# SCH_RTC6705_V0_1_2025-12-21.net
KiCad netlist of a schematic drawn in EasyEDA
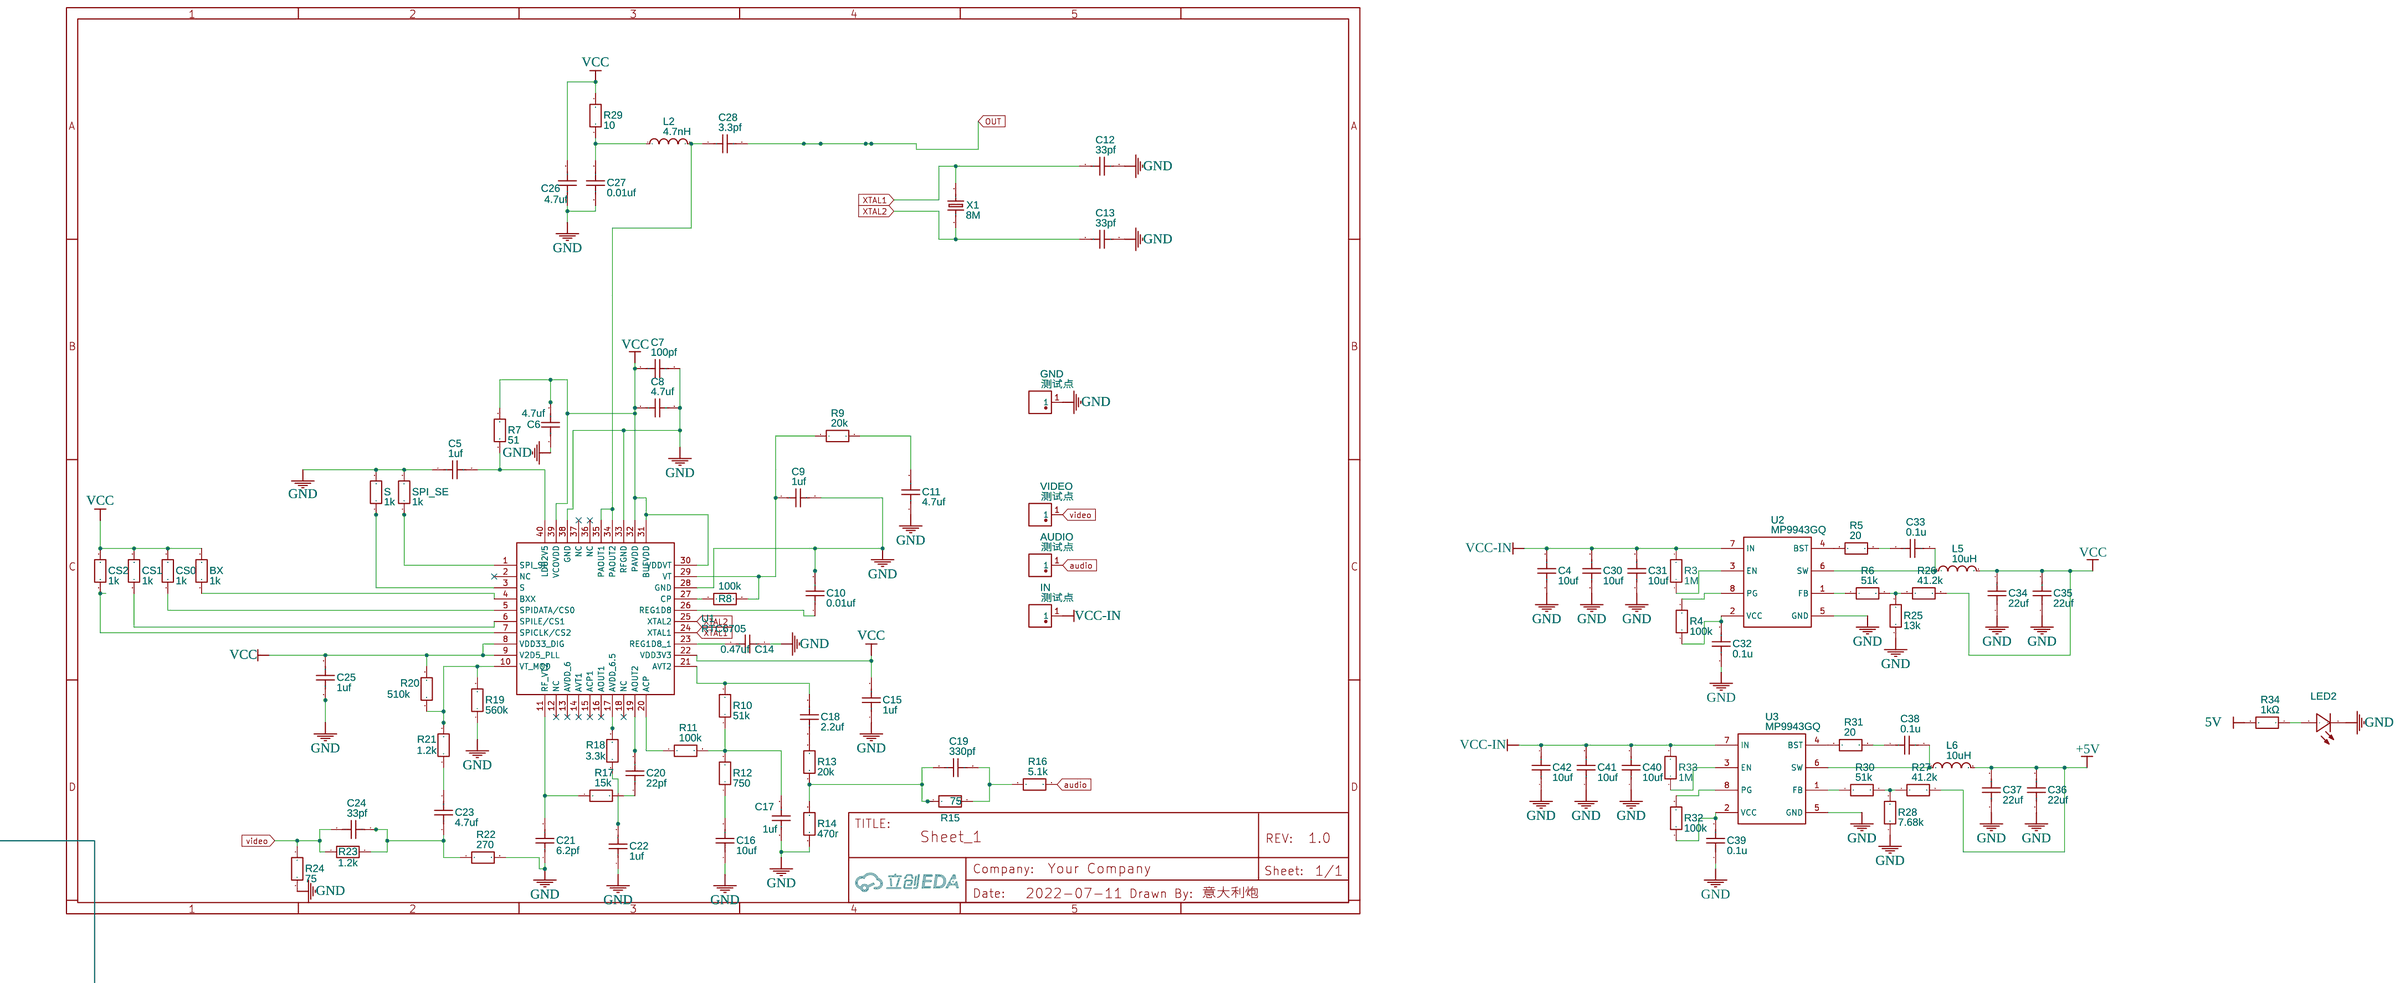
[diagram p0: 稳压和调频]
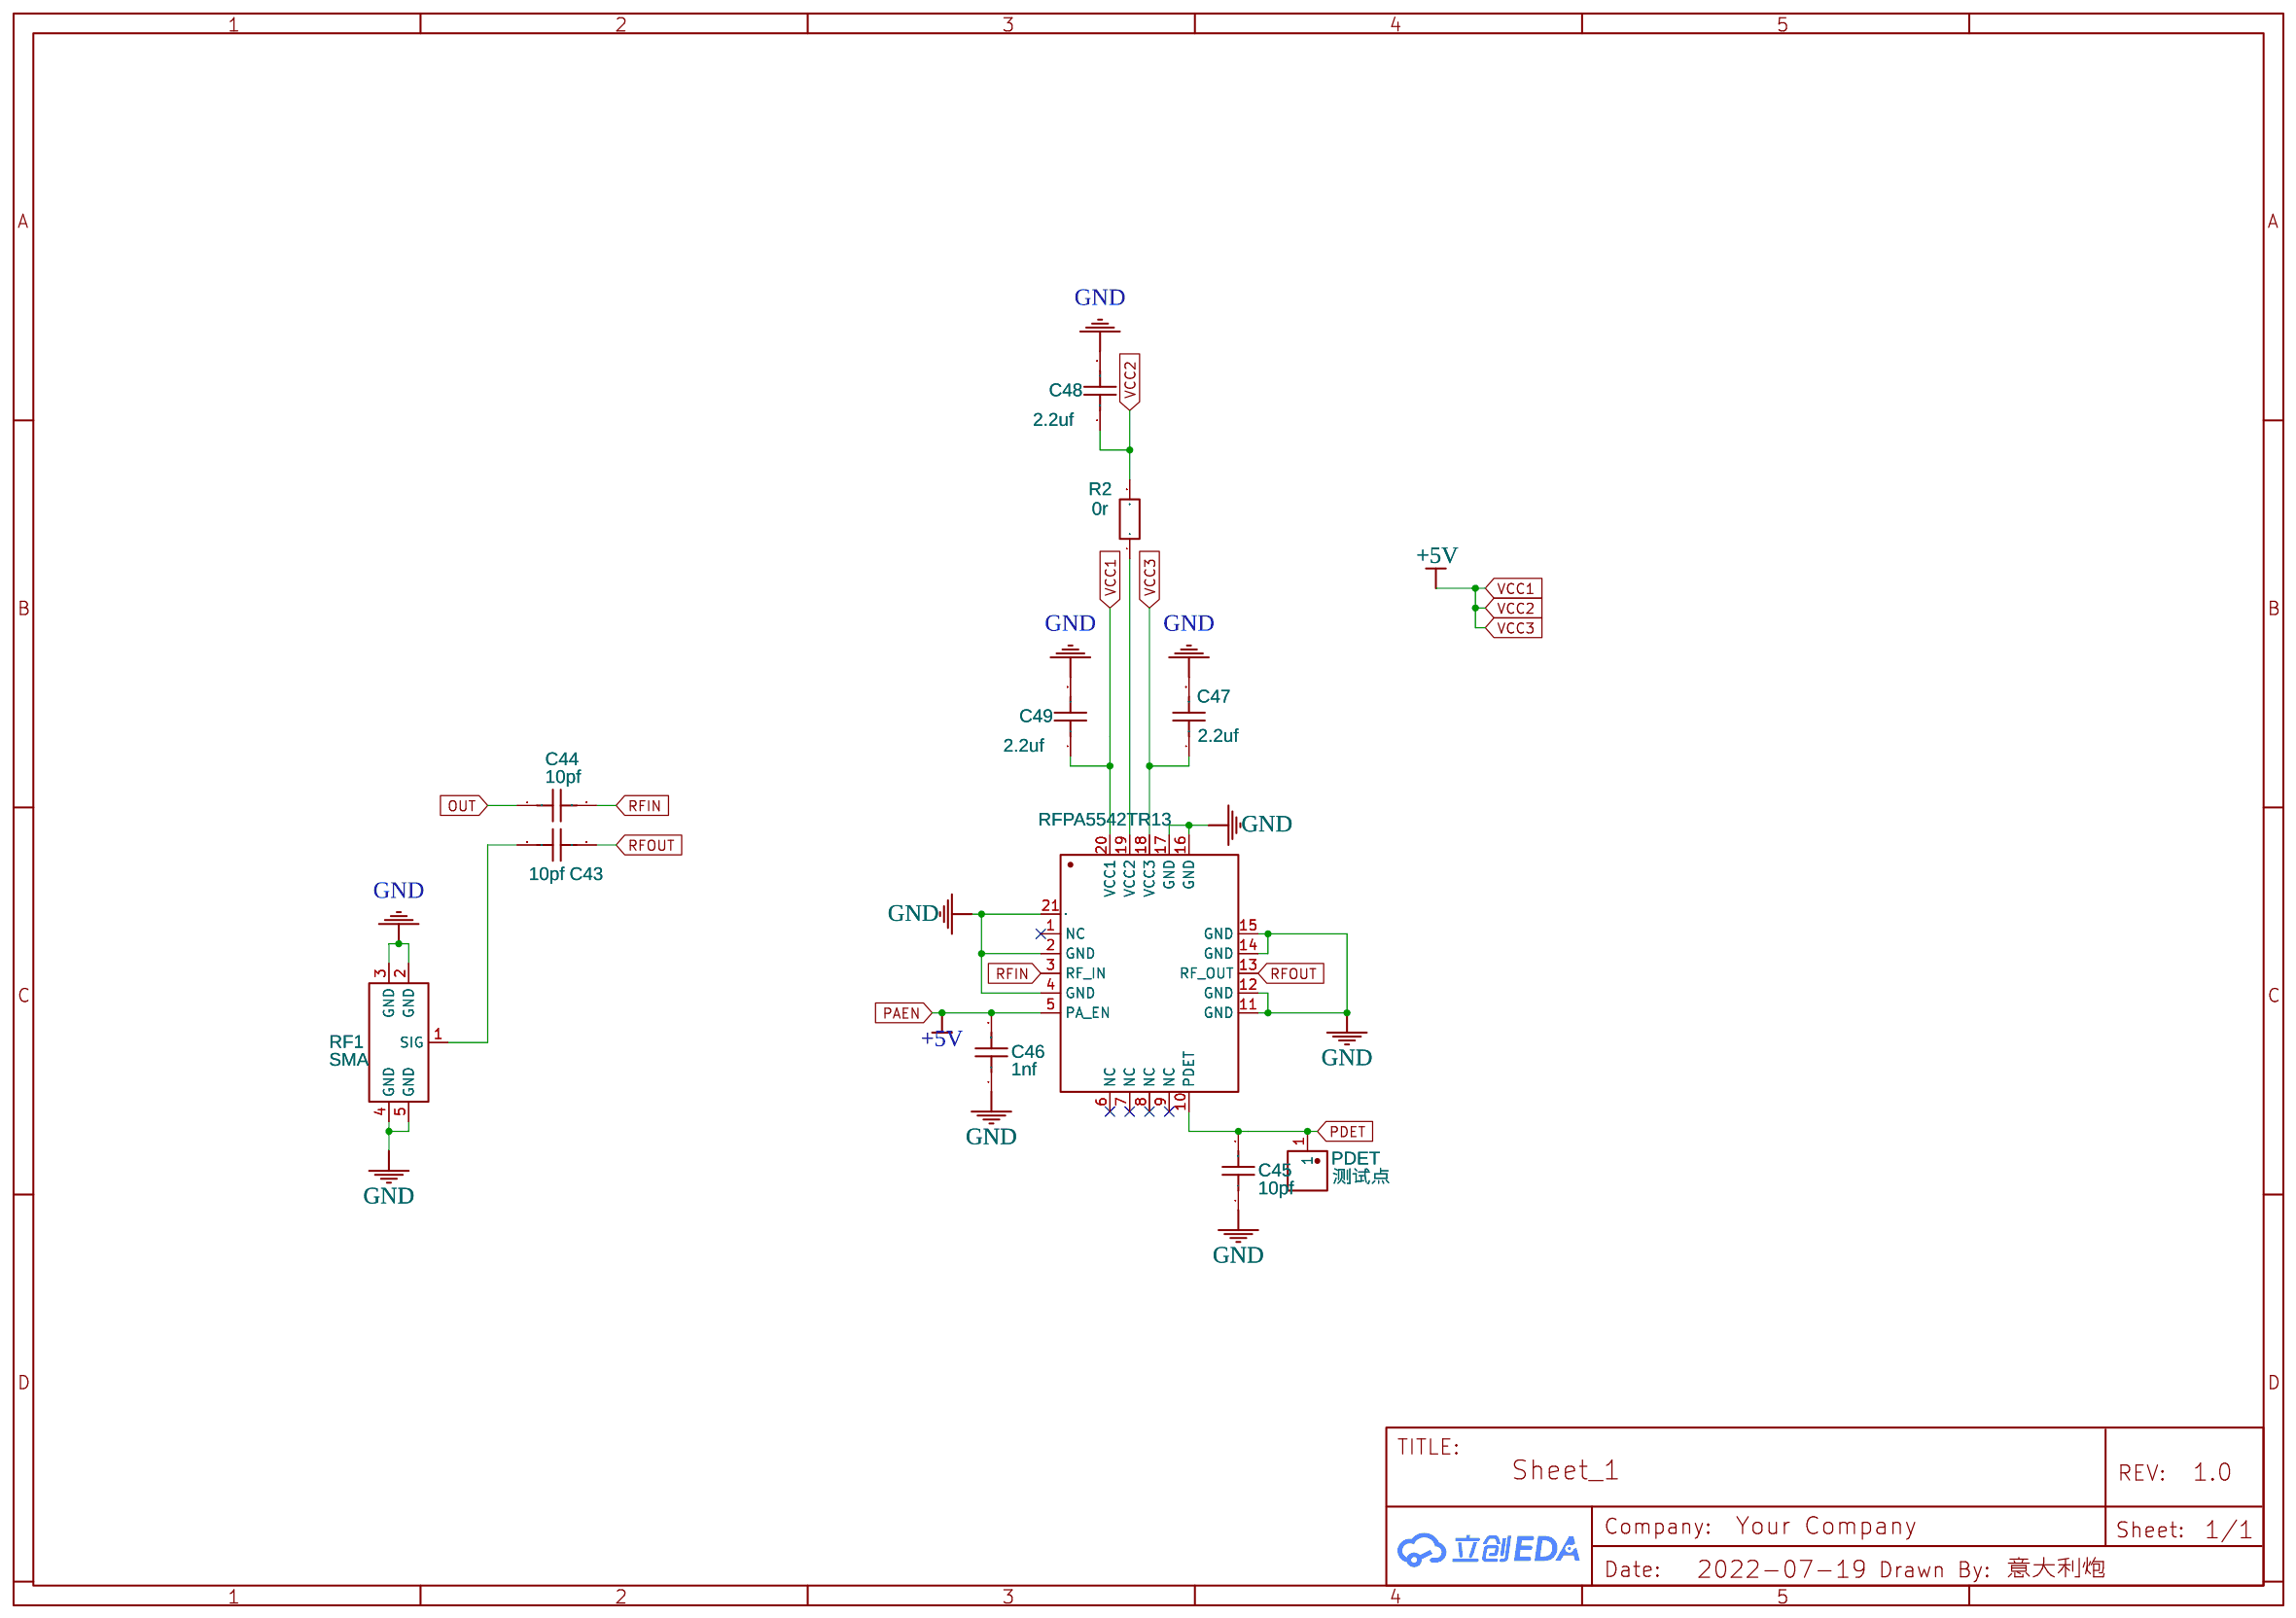
[diagram p1: 2W放大器]

(export (version "E")
  (design (tool "Eeschema 10.0.6"))
  (components
    (comp (ref "AUDIO") (value "测试点") (libsource (lib "") (part "测试点_3")))
    (comp (ref "BX") (value "1k") (libsource (lib "") (part "R_0603_EU_5")))
    (comp (ref "C4") (value "10uf") (libsource (lib "") (part "C_0603_US_1")))
    (comp (ref "C5") (value "1uf") (libsource (lib "") (part "C_0603_US")))
    (comp (ref "C6") (value "4.7uf") (libsource (lib "") (part "C_0603_US_1")))
    (comp (ref "C7") (value "100pf") (libsource (lib "") (part "C_0603_US")))
    (comp (ref "C8") (value "4.7uf") (libsource (lib "") (part "C_0603_US")))
    (comp (ref "C9") (value "1uf") (libsource (lib "") (part "C_0603_US")))
    (comp (ref "C10") (value "0.01uf") (libsource (lib "") (part "C_0603_US_1")))
    (comp (ref "C11") (value "4.7uf") (libsource (lib "") (part "C_0603_US_1")))
    (comp (ref "C12") (value "33pf") (libsource (lib "") (part "C_0603_US")))
    (comp (ref "C13") (value "33pf") (libsource (lib "") (part "C_0603_US")))
    (comp (ref "C14") (value "0.47uf") (libsource (lib "") (part "C_0603_US")))
    (comp (ref "C15") (value "1uf") (libsource (lib "") (part "C_0603_US_1")))
    (comp (ref "C16") (value "10uf") (libsource (lib "") (part "C_0603_US_1")))
    (comp (ref "C17") (value "1uf") (libsource (lib "") (part "C_0603_US_1")))
    (comp (ref "C18") (value "2.2uf") (libsource (lib "") (part "C_0603_US_1")))
    (comp (ref "C19") (value "330pf") (libsource (lib "") (part "C_0603_US")))
    (comp (ref "C20") (value "22pf") (libsource (lib "") (part "C_0603_US_1")))
    (comp (ref "C21") (value "6.2pf") (libsource (lib "") (part "C_0603_US_1")))
    (comp (ref "C22") (value "1uf") (libsource (lib "") (part "C_0603_US_1")))
    (comp (ref "C23") (value "4.7uf") (libsource (lib "") (part "C_0603_US_1")))
    (comp (ref "C24") (value "33pf") (libsource (lib "") (part "C_0603_US")))
    (comp (ref "C25") (value "1uf") (libsource (lib "") (part "C_0603_US_1")))
    (comp (ref "C26") (value "4.7uf") (libsource (lib "") (part "C_0603_US_1")))
    (comp (ref "C27") (value "0.01uf") (libsource (lib "") (part "C_0603_US_1")))
    (comp (ref "C28") (value "3.3pf") (libsource (lib "") (part "C_0603_US")))
    (comp (ref "C30") (value "10uf") (libsource (lib "") (part "C_0603_US_1")))
    (comp (ref "C31") (value "10uf") (libsource (lib "") (part "C_0603_US_1")))
    (comp (ref "C32") (value "0.1u") (libsource (lib "") (part "C_0603_US_1")))
    (comp (ref "C33") (value "0.1u") (libsource (lib "") (part "C_0603_US")))
    (comp (ref "C34") (value "22uf") (libsource (lib "") (part "C_0805_US")))
    (comp (ref "C35") (value "22uf") (libsource (lib "") (part "C_0805_US")))
    (comp (ref "C36") (value "22uf") (libsource (lib "") (part "C_0805_US")))
    (comp (ref "C37") (value "22uf") (libsource (lib "") (part "C_0805_US")))
    (comp (ref "C38") (value "0.1u") (libsource (lib "") (part "C_0603_US")))
    (comp (ref "C39") (value "0.1u") (libsource (lib "") (part "C_0603_US_1")))
    (comp (ref "C40") (value "10uf") (libsource (lib "") (part "C_0603_US_1")))
    (comp (ref "C41") (value "10uf") (libsource (lib "") (part "C_0603_US_1")))
    (comp (ref "C42") (value "10uf") (libsource (lib "") (part "C_0603_US_1")))
    (comp (ref "CS0") (value "1k") (libsource (lib "") (part "R_0603_EU")))
    (comp (ref "CS1") (value "1k") (libsource (lib "") (part "R_0603_EU")))
    (comp (ref "CS2") (value "1k") (libsource (lib "") (part "R_0603_EU")))
    (comp (ref "GND") (value "测试点") (libsource (lib "") (part "测试点_1")))
    (comp (ref "IN") (value "测试点") (libsource (lib "") (part "测试点")))
    (comp (ref "L2")
      (value "4.7nH")
      (fields (field (name "Manufacturer Part") "SDCL1608C4N7STDF") (field (name "Manufacturer") "Sunlord"))
      (libsource (lib "") (part "SDCL1608C4N7STDF"))
    )
    (comp (ref "L5")
      (value "10uH")
      (fields (field (name "Manufacturer Part") "PHC0420-100M-T") (field (name "Manufacturer") "EMTEK"))
      (libsource (lib "") (part "PHC0420-100M-T"))
    )
    (comp (ref "L6")
      (value "10uH")
      (fields (field (name "Manufacturer Part") "PHC0420-100M-T") (field (name "Manufacturer") "EMTEK"))
      (libsource (lib "") (part "PHC0420-100M-T"))
    )
    (comp (ref "LED2")
      (value "LTST-C170KRKT")
      (fields (field (name "Manufacturer") "LITEON"))
      (libsource (lib "") (part "LTST-C170KRKT"))
    )
    (comp (ref "R3") (value "1M") (libsource (lib "") (part "R_0603_EU_2")))
    (comp (ref "R4") (value "100k") (libsource (lib "") (part "R_0603_EU_2")))
    (comp (ref "R5") (value "20") (libsource (lib "") (part "R_0603_EU_1")))
    (comp (ref "R6") (value "51k") (libsource (lib "") (part "R_0402_EU")))
    (comp (ref "R7") (value "51") (libsource (lib "") (part "R_0603_EU_2")))
    (comp (ref "R8") (value "100k") (libsource (lib "") (part "R_0603_EU_1")))
    (comp (ref "R9") (value "20k") (libsource (lib "") (part "R_0603_EU_1")))
    (comp (ref "R10") (value "51k") (libsource (lib "") (part "R_0603_EU_2")))
    (comp (ref "R11") (value "100k") (libsource (lib "") (part "R_0603_EU_1")))
    (comp (ref "R12") (value "750") (libsource (lib "") (part "R_0603_EU_2")))
    (comp (ref "R13") (value "20k") (libsource (lib "") (part "R_0603_EU_2")))
    (comp (ref "R14") (value "470r") (libsource (lib "") (part "R_0603_EU_2")))
    (comp (ref "R15") (value "75") (libsource (lib "") (part "R_0603_EU_1")))
    (comp (ref "R16") (value "5.1k") (libsource (lib "") (part "R_0603_EU_1")))
    (comp (ref "R17") (value "15k") (libsource (lib "") (part "R_0603_EU_1")))
    (comp (ref "R18") (value "3.3k") (libsource (lib "") (part "R_0603_EU_2")))
    (comp (ref "R19") (value "560k") (libsource (lib "") (part "R_0603_EU_2")))
    (comp (ref "R20") (value "510k") (libsource (lib "") (part "R_0603_EU_2")))
    (comp (ref "R21") (value "1.2k") (libsource (lib "") (part "R_0603_EU_2")))
    (comp (ref "R22") (value "270") (libsource (lib "") (part "R_0603_EU_1")))
    (comp (ref "R23") (value "1.2k") (libsource (lib "") (part "R_0603_EU_1")))
    (comp (ref "R24") (value "75") (libsource (lib "") (part "R_0603_EU_2")))
    (comp (ref "R25") (value "13k") (libsource (lib "") (part "R_0402_EU_1")))
    (comp (ref "R26") (value "41.2k") (libsource (lib "") (part "R_0402_EU")))
    (comp (ref "R27") (value "41.2k") (libsource (lib "") (part "R_0402_EU")))
    (comp (ref "R28") (value "7.68k") (libsource (lib "") (part "R_0402_EU_1")))
    (comp (ref "R29") (value "10") (libsource (lib "") (part "R_0603_EU_2")))
    (comp (ref "R30") (value "51k") (libsource (lib "") (part "R_0402_EU")))
    (comp (ref "R31") (value "20") (libsource (lib "") (part "R_0603_EU_1")))
    (comp (ref "R32") (value "100k") (libsource (lib "") (part "R_0603_EU_2")))
    (comp (ref "R33") (value "1M") (libsource (lib "") (part "R_0603_EU_2")))
    (comp (ref "R34")
      (value "1kΩ")
      (fields (field (name "Manufacturer Part") "ESR10EZPF1001") (field (name "Manufacturer") "ROHM Semicon"))
      (libsource (lib "") (part "ESR10EZPF1001"))
    )
    (comp (ref "S") (value "1k") (libsource (lib "") (part "R_0603_EU_4")))
    (comp (ref "SPI_SE") (value "1k") (libsource (lib "") (part "R_0603_EU_3")))
    (comp (ref "U1")
      (value "RTC6705")
      (fields (field (name "Manufacturer") "Richwave"))
      (libsource (lib "") (part "RTC6705"))
    )
    (comp (ref "U2")
      (value "MP9943GQ")
      (fields (field (name "Manufacturer") "MPS"))
      (libsource (lib "") (part "MP9943GQ"))
    )
    (comp (ref "U3")
      (value "MP9943GQ")
      (fields (field (name "Manufacturer") "MPS"))
      (libsource (lib "") (part "MP9943GQ"))
    )
    (comp (ref "VIDEO") (value "测试点") (libsource (lib "") (part "测试点_2")))
    (comp (ref "X1")
      (value "8M")
      (fields (field (name "Manufacturer Part") "8M晶振"))
      (libsource (lib "") (part "8M晶振_C9900021502"))
    )
    (comp (ref "C43") (value "10pf") (libsource (lib "") (part "C_0603_US")))
    (comp (ref "C44") (value "10pf") (libsource (lib "") (part "C_0603_US")))
    (comp (ref "C45") (value "10pf") (libsource (lib "") (part "C_0603_US_1")))
    (comp (ref "C46") (value "1nf") (libsource (lib "") (part "C_0603_US_1")))
    (comp (ref "C47") (value "2.2uf") (libsource (lib "") (part "C_0603_US_1")))
    (comp (ref "C48") (value "2.2uf") (libsource (lib "") (part "C_0603_US_1")))
    (comp (ref "C49") (value "2.2uf") (libsource (lib "") (part "C_0603_US_1")))
    (comp (ref "PDET") (value "测试点") (libsource (lib "") (part "测试点")))
    (comp (ref "R2") (value "0r") (libsource (lib "") (part "R_0603_EU")))
    (comp (ref "RF1")
      (value "SMA")
      (fields (field (name "Manufacturer Part") "HJ-SMA023") (field (name "Manufacturer") "皇捷"))
      (libsource (lib "") (part "SMA"))
    )
    (comp (ref "U5")
      (value "RFPA5542TR13")
      (fields (field (name "Manufacturer") "Qorvo"))
      (libsource (lib "") (part "RFPA5542TR13"))
    )
  )
  (nets
    (net (code "1") (name "5V") (class "Default")
      (node (ref "R34") (pin "2") (pinfunction "2_2") (pintype "unspecified"))
    )
    (net (code "2") (name "GND") (class "Default")
      (node (ref "C10") (pin "2") (pinfunction "2_2") (pintype "unspecified"))
      (node (ref "C11") (pin "1") (pinfunction "1_1") (pintype "unspecified"))
      (node (ref "C12") (pin "2") (pinfunction "2_2") (pintype "unspecified"))
      (node (ref "C13") (pin "2") (pinfunction "2_2") (pintype "unspecified"))
      (node (ref "C14") (pin "2") (pinfunction "2_2") (pintype "unspecified"))
      (node (ref "C15") (pin "1") (pinfunction "1_1") (pintype "unspecified"))
      (node (ref "C16") (pin "1") (pinfunction "1_1") (pintype "unspecified"))
      (node (ref "C17") (pin "1") (pinfunction "1_1") (pintype "unspecified"))
      (node (ref "C21") (pin "1") (pinfunction "1_1") (pintype "unspecified"))
      (node (ref "C22") (pin "1") (pinfunction "1_1") (pintype "unspecified"))
      (node (ref "C25") (pin "1") (pinfunction "1_1") (pintype "unspecified"))
      (node (ref "C26") (pin "1") (pinfunction "1_1") (pintype "unspecified"))
      (node (ref "C27") (pin "1") (pinfunction "1_1") (pintype "unspecified"))
      (node (ref "C30") (pin "1") (pinfunction "1_1") (pintype "unspecified"))
      (node (ref "C31") (pin "1") (pinfunction "1_1") (pintype "unspecified"))
      (node (ref "C32") (pin "1") (pinfunction "1_1") (pintype "unspecified"))
      (node (ref "C34") (pin "1") (pinfunction "1_1") (pintype "unspecified"))
      (node (ref "C35") (pin "1") (pinfunction "1_1") (pintype "unspecified"))
      (node (ref "C36") (pin "1") (pinfunction "1_1") (pintype "unspecified"))
      (node (ref "C37") (pin "1") (pinfunction "1_1") (pintype "unspecified"))
      (node (ref "C39") (pin "1") (pinfunction "1_1") (pintype "unspecified"))
      (node (ref "C4") (pin "1") (pinfunction "1_1") (pintype "unspecified"))
      (node (ref "C40") (pin "1") (pinfunction "1_1") (pintype "unspecified"))
      (node (ref "C41") (pin "1") (pinfunction "1_1") (pintype "unspecified"))
      (node (ref "C42") (pin "1") (pinfunction "1_1") (pintype "unspecified"))
      (node (ref "C45") (pin "1") (pinfunction "1_1") (pintype "unspecified"))
      (node (ref "C46") (pin "1") (pinfunction "1_1") (pintype "unspecified"))
      (node (ref "C47") (pin "2") (pinfunction "2_2") (pintype "unspecified"))
      (node (ref "C48") (pin "2") (pinfunction "2_2") (pintype "unspecified"))
      (node (ref "C49") (pin "2") (pinfunction "2_2") (pintype "unspecified"))
      (node (ref "C5") (pin "1") (pinfunction "1_1") (pintype "unspecified"))
      (node (ref "C6") (pin "1") (pinfunction "1_1") (pintype "unspecified"))
      (node (ref "C7") (pin "2") (pinfunction "2_2") (pintype "unspecified"))
      (node (ref "C8") (pin "2") (pinfunction "2_2") (pintype "unspecified"))
      (node (ref "C9") (pin "2") (pinfunction "2_2") (pintype "unspecified"))
      (node (ref "GND") (pin "1") (pinfunction "1_1") (pintype "unspecified"))
      (node (ref "LED2") (pin "1") (pinfunction "-_1") (pintype "unspecified"))
      (node (ref "R14") (pin "1") (pinfunction "1_1") (pintype "unspecified"))
      (node (ref "R19") (pin "1") (pinfunction "1_1") (pintype "unspecified"))
      (node (ref "R22") (pin "2") (pinfunction "2_2") (pintype "unspecified"))
      (node (ref "R24") (pin "1") (pinfunction "1_1") (pintype "unspecified"))
      (node (ref "R25") (pin "1") (pinfunction "1_1") (pintype "unspecified"))
      (node (ref "R28") (pin "1") (pinfunction "1_1") (pintype "unspecified"))
      (node (ref "RF1") (pin "2") (pinfunction "GND_2") (pintype "unspecified"))
      (node (ref "RF1") (pin "3") (pinfunction "GND_3") (pintype "unspecified"))
      (node (ref "RF1") (pin "4") (pinfunction "GND_4") (pintype "unspecified"))
      (node (ref "RF1") (pin "5") (pinfunction "GND_5") (pintype "unspecified"))
      (node (ref "S") (pin "2") (pinfunction "2_2") (pintype "unspecified"))
      (node (ref "SPI_SE") (pin "2") (pinfunction "2_2") (pintype "unspecified"))
      (node (ref "U1") (pin "28") (pinfunction "GND_28") (pintype "unspecified"))
      (node (ref "U1") (pin "33") (pinfunction "RFGND_33") (pintype "unspecified"))
      (node (ref "U1") (pin "38") (pinfunction "GND_38") (pintype "unspecified"))
      (node (ref "U2") (pin "5") (pinfunction "GND_5") (pintype "unspecified"))
      (node (ref "U3") (pin "5") (pinfunction "GND_5") (pintype "unspecified"))
      (node (ref "U5") (pin "11") (pinfunction "GND_11") (pintype "unspecified"))
      (node (ref "U5") (pin "12") (pinfunction "GND_12") (pintype "unspecified"))
      (node (ref "U5") (pin "14") (pinfunction "GND_14") (pintype "unspecified"))
      (node (ref "U5") (pin "15") (pinfunction "GND_15") (pintype "unspecified"))
      (node (ref "U5") (pin "16") (pinfunction "GND_16") (pintype "unspecified"))
      (node (ref "U5") (pin "17") (pinfunction "GND_17") (pintype "unspecified"))
      (node (ref "U5") (pin "2") (pinfunction "GND_2") (pintype "unspecified"))
      (node (ref "U5") (pin "21") (pinfunction "PAD_21") (pintype "unspecified"))
      (node (ref "U5") (pin "4") (pinfunction "GND_4") (pintype "unspecified"))
    )
    (net (code "3") (name "Net-(C11-Pad2)") (class "Default")
      (node (ref "C11") (pin "2") (pinfunction "2_2") (pintype "unspecified"))
      (node (ref "R9") (pin "2") (pinfunction "2_2") (pintype "unspecified"))
    )
    (net (code "4") (name "Net-(C16-Pad2)") (class "Default")
      (node (ref "C16") (pin "2") (pinfunction "2_2") (pintype "unspecified"))
      (node (ref "R12") (pin "1") (pinfunction "1_1") (pintype "unspecified"))
    )
    (net (code "5") (name "Net-(C17-Pad2)") (class "Default")
      (node (ref "C17") (pin "2") (pinfunction "2_2") (pintype "unspecified"))
      (node (ref "R10") (pin "1") (pinfunction "1_1") (pintype "unspecified"))
      (node (ref "R11") (pin "2") (pinfunction "2_2") (pintype "unspecified"))
      (node (ref "R12") (pin "2") (pinfunction "2_2") (pintype "unspecified"))
    )
    (net (code "6") (name "Net-(C18-Pad1)") (class "Default")
      (node (ref "C18") (pin "1") (pinfunction "1_1") (pintype "unspecified"))
      (node (ref "R13") (pin "2") (pinfunction "2_2") (pintype "unspecified"))
    )
    (net (code "7") (name "Net-(C19-Pad1)") (class "Default")
      (node (ref "C19") (pin "1") (pinfunction "1_1") (pintype "unspecified"))
      (node (ref "R13") (pin "1") (pinfunction "1_1") (pintype "unspecified"))
      (node (ref "R14") (pin "2") (pinfunction "2_2") (pintype "unspecified"))
      (node (ref "R15") (pin "1") (pinfunction "1_1") (pintype "unspecified"))
    )
    (net (code "8") (name "Net-(C19-Pad2)") (class "Default")
      (node (ref "C19") (pin "2") (pinfunction "2_2") (pintype "unspecified"))
      (node (ref "R15") (pin "2") (pinfunction "2_2") (pintype "unspecified"))
      (node (ref "R16") (pin "1") (pinfunction "1_1") (pintype "unspecified"))
    )
    (net (code "9") (name "Net-(C20-Pad1)") (class "Default")
      (node (ref "C20") (pin "1") (pinfunction "1_1") (pintype "unspecified"))
      (node (ref "R17") (pin "2") (pinfunction "2_2") (pintype "unspecified"))
    )
    (net (code "10") (name "Net-(C22-Pad2)") (class "Default")
      (node (ref "C22") (pin "2") (pinfunction "2_2") (pintype "unspecified"))
      (node (ref "R18") (pin "1") (pinfunction "1_1") (pintype "unspecified"))
    )
    (net (code "11") (name "Net-(C23-Pad1)") (class "Default")
      (node (ref "C23") (pin "1") (pinfunction "1_1") (pintype "unspecified"))
      (node (ref "C24") (pin "2") (pinfunction "2_2") (pintype "unspecified"))
      (node (ref "R22") (pin "1") (pinfunction "1_1") (pintype "unspecified"))
      (node (ref "R23") (pin "2") (pinfunction "2_2") (pintype "unspecified"))
    )
    (net (code "12") (name "Net-(C23-Pad2)") (class "Default")
      (node (ref "C23") (pin "2") (pinfunction "2_2") (pintype "unspecified"))
      (node (ref "R21") (pin "1") (pinfunction "1_1") (pintype "unspecified"))
    )
    (net (code "13") (name "Net-(C27-Pad2)") (class "Default")
      (node (ref "C27") (pin "2") (pinfunction "2_2") (pintype "unspecified"))
      (node (ref "L2") (pin "1") (pinfunction "1_1") (pintype "unspecified"))
      (node (ref "R29") (pin "1") (pinfunction "1_1") (pintype "unspecified"))
    )
    (net (code "14") (name "Net-(C33-Pad1)") (class "Default")
      (node (ref "C33") (pin "1") (pinfunction "1_1") (pintype "unspecified"))
      (node (ref "R5") (pin "2") (pinfunction "2_2") (pintype "unspecified"))
    )
    (net (code "15") (name "Net-(C38-Pad1)") (class "Default")
      (node (ref "C38") (pin "1") (pinfunction "1_1") (pintype "unspecified"))
      (node (ref "R31") (pin "2") (pinfunction "2_2") (pintype "unspecified"))
    )
    (net (code "16") (name "Net-(LED2-+)") (class "Default")
      (node (ref "LED2") (pin "2") (pinfunction "+_2") (pintype "unspecified"))
      (node (ref "R34") (pin "1") (pinfunction "1_1") (pintype "unspecified"))
    )
    (net (code "17") (name "Net-(R25-Pad2)") (class "Default")
      (node (ref "R25") (pin "2") (pinfunction "2_2") (pintype "unspecified"))
      (node (ref "R26") (pin "1") (pinfunction "1_1") (pintype "unspecified"))
      (node (ref "R6") (pin "2") (pinfunction "2_2") (pintype "unspecified"))
    )
    (net (code "18") (name "Net-(R27-Pad1)") (class "Default")
      (node (ref "R27") (pin "1") (pinfunction "1_1") (pintype "unspecified"))
      (node (ref "R28") (pin "2") (pinfunction "2_2") (pintype "unspecified"))
      (node (ref "R30") (pin "2") (pinfunction "2_2") (pintype "unspecified"))
    )
    (net (code "19") (name "Net-(RF1-SIG)") (class "Default")
      (node (ref "C43") (pin "1") (pinfunction "1_1") (pintype "unspecified"))
      (node (ref "RF1") (pin "1") (pinfunction "SIG_1") (pintype "unspecified"))
    )
    (net (code "20") (name "Net-(U1-ACP)") (class "Default")
      (node (ref "R11") (pin "1") (pinfunction "1_1") (pintype "unspecified"))
      (node (ref "U1") (pin "20") (pinfunction "ACP_20") (pintype "unspecified"))
    )
    (net (code "21") (name "Net-(U1-AOUT2)") (class "Default")
      (node (ref "C20") (pin "2") (pinfunction "2_2") (pintype "unspecified"))
      (node (ref "U1") (pin "19") (pinfunction "AOUT2_19") (pintype "unspecified"))
    )
    (net (code "22") (name "Net-(U1-AVDD_6.5)") (class "Default")
      (node (ref "R18") (pin "2") (pinfunction "2_2") (pintype "unspecified"))
      (node (ref "U1") (pin "17") (pinfunction "AVDD_6.5_17") (pintype "unspecified"))
    )
    (net (code "23") (name "Net-(U1-AVT2)") (class "Default")
      (node (ref "C18") (pin "2") (pinfunction "2_2") (pintype "unspecified"))
      (node (ref "R10") (pin "2") (pinfunction "2_2") (pintype "unspecified"))
      (node (ref "U1") (pin "21") (pinfunction "AVT2_21") (pintype "unspecified"))
    )
    (net (code "24") (name "Net-(U1-BXX)") (class "Default")
      (node (ref "BX") (pin "1") (pinfunction "1_1") (pintype "unspecified"))
      (node (ref "U1") (pin "4") (pinfunction "BXX_4") (pintype "unspecified"))
    )
    (net (code "25") (name "Net-(U1-CP)") (class "Default")
      (node (ref "R8") (pin "1") (pinfunction "1_1") (pintype "unspecified"))
      (node (ref "U1") (pin "27") (pinfunction "CP_27") (pintype "unspecified"))
    )
    (net (code "26") (name "Net-(U1-LDO2V5)") (class "Default")
      (node (ref "C5") (pin "2") (pinfunction "2_2") (pintype "unspecified"))
      (node (ref "R7") (pin "1") (pinfunction "1_1") (pintype "unspecified"))
      (node (ref "U1") (pin "40") (pinfunction "LDO2V5_40") (pintype "unspecified"))
    )
    (net (code "27") (name "Net-(U1-PAOUT1)") (class "Default")
      (node (ref "C28") (pin "1") (pinfunction "1_1") (pintype "unspecified"))
      (node (ref "L2") (pin "2") (pinfunction "2_2") (pintype "unspecified"))
      (node (ref "U1") (pin "34") (pinfunction "PAOUT2_34") (pintype "unspecified"))
      (node (ref "U1") (pin "35") (pinfunction "PAOUT1_35") (pintype "unspecified"))
    )
    (net (code "28") (name "Net-(U1-REG1D8)") (class "Default")
      (node (ref "C10") (pin "1") (pinfunction "1_1") (pintype "unspecified"))
      (node (ref "U1") (pin "26") (pinfunction "REG1D8_26") (pintype "unspecified"))
    )
    (net (code "29") (name "Net-(U1-REG1D8_1)") (class "Default")
      (node (ref "C14") (pin "1") (pinfunction "1_1") (pintype "unspecified"))
      (node (ref "U1") (pin "23") (pinfunction "REG1D8_1_23") (pintype "unspecified"))
    )
    (net (code "30") (name "Net-(U1-RF_VT2)") (class "Default")
      (node (ref "C21") (pin "2") (pinfunction "2_2") (pintype "unspecified"))
      (node (ref "R17") (pin "1") (pinfunction "1_1") (pintype "unspecified"))
      (node (ref "U1") (pin "11") (pinfunction "RF_VT2_11") (pintype "unspecified"))
    )
    (net (code "31") (name "Net-(U1-S)") (class "Default")
      (node (ref "S") (pin "1") (pinfunction "1_1") (pintype "unspecified"))
      (node (ref "U1") (pin "3") (pinfunction "S_3") (pintype "unspecified"))
    )
    (net (code "32") (name "Net-(U1-SPICLK{slash}CS2)") (class "Default")
      (node (ref "CS2") (pin "1") (pinfunction "1_1") (pintype "unspecified"))
      (node (ref "U1") (pin "7") (pinfunction "SPICLK/CS2_7") (pintype "unspecified"))
    )
    (net (code "33") (name "Net-(U1-SPIDATA{slash}CS0)") (class "Default")
      (node (ref "CS0") (pin "1") (pinfunction "1_1") (pintype "unspecified"))
      (node (ref "U1") (pin "5") (pinfunction "SPIDATA/CS0_5") (pintype "unspecified"))
    )
    (net (code "34") (name "Net-(U1-SPILE{slash}CS1)") (class "Default")
      (node (ref "CS1") (pin "1") (pinfunction "1_1") (pintype "unspecified"))
      (node (ref "U1") (pin "6") (pinfunction "SPILE/CS1_6") (pintype "unspecified"))
    )
    (net (code "35") (name "Net-(U1-SPI_SE)") (class "Default")
      (node (ref "SPI_SE") (pin "1") (pinfunction "1_1") (pintype "unspecified"))
      (node (ref "U1") (pin "1") (pinfunction "SPI_SE_1") (pintype "unspecified"))
    )
    (net (code "36") (name "Net-(U1-VT)") (class "Default")
      (node (ref "C9") (pin "1") (pinfunction "1_1") (pintype "unspecified"))
      (node (ref "R8") (pin "2") (pinfunction "2_2") (pintype "unspecified"))
      (node (ref "R9") (pin "1") (pinfunction "1_1") (pintype "unspecified"))
      (node (ref "U1") (pin "29") (pinfunction "VT_29") (pintype "unspecified"))
    )
    (net (code "37") (name "Net-(U1-VT_MOD)") (class "Default")
      (node (ref "R19") (pin "2") (pinfunction "2_2") (pintype "unspecified"))
      (node (ref "R20") (pin "1") (pinfunction "1_1") (pintype "unspecified"))
      (node (ref "R21") (pin "2") (pinfunction "2_2") (pintype "unspecified"))
      (node (ref "U1") (pin "10") (pinfunction "VT_MOD_10") (pintype "unspecified"))
    )
    (net (code "38") (name "Net-(U2-BST)") (class "Default")
      (node (ref "R5") (pin "1") (pinfunction "1_1") (pintype "unspecified"))
      (node (ref "U2") (pin "4") (pinfunction "BST_4") (pintype "unspecified"))
    )
    (net (code "39") (name "Net-(U2-EN)") (class "Default")
      (node (ref "R3") (pin "1") (pinfunction "1_1") (pintype "unspecified"))
      (node (ref "U2") (pin "3") (pinfunction "EN_3") (pintype "unspecified"))
    )
    (net (code "40") (name "Net-(U2-FB)") (class "Default")
      (node (ref "R6") (pin "1") (pinfunction "1_1") (pintype "unspecified"))
      (node (ref "U2") (pin "1") (pinfunction "FB_1") (pintype "unspecified"))
    )
    (net (code "41") (name "Net-(U2-PG)") (class "Default")
      (node (ref "R4") (pin "2") (pinfunction "2_2") (pintype "unspecified"))
      (node (ref "U2") (pin "8") (pinfunction "PG_8") (pintype "unspecified"))
    )
    (net (code "42") (name "Net-(U2-SW)") (class "Default")
      (node (ref "C33") (pin "2") (pinfunction "2_2") (pintype "unspecified"))
      (node (ref "L5") (pin "1") (pinfunction "1_1") (pintype "unspecified"))
      (node (ref "U2") (pin "6") (pinfunction "SW_6") (pintype "unspecified"))
    )
    (net (code "43") (name "Net-(U2-VCC)") (class "Default")
      (node (ref "C32") (pin "2") (pinfunction "2_2") (pintype "unspecified"))
      (node (ref "R4") (pin "1") (pinfunction "1_1") (pintype "unspecified"))
      (node (ref "U2") (pin "2") (pinfunction "VCC_2") (pintype "unspecified"))
    )
    (net (code "44") (name "Net-(U3-BST)") (class "Default")
      (node (ref "R31") (pin "1") (pinfunction "1_1") (pintype "unspecified"))
      (node (ref "U3") (pin "4") (pinfunction "BST_4") (pintype "unspecified"))
    )
    (net (code "45") (name "Net-(U3-EN)") (class "Default")
      (node (ref "R33") (pin "1") (pinfunction "1_1") (pintype "unspecified"))
      (node (ref "U3") (pin "3") (pinfunction "EN_3") (pintype "unspecified"))
    )
    (net (code "46") (name "Net-(U3-FB)") (class "Default")
      (node (ref "R30") (pin "1") (pinfunction "1_1") (pintype "unspecified"))
      (node (ref "U3") (pin "1") (pinfunction "FB_1") (pintype "unspecified"))
    )
    (net (code "47") (name "Net-(U3-PG)") (class "Default")
      (node (ref "R32") (pin "2") (pinfunction "2_2") (pintype "unspecified"))
      (node (ref "U3") (pin "8") (pinfunction "PG_8") (pintype "unspecified"))
    )
    (net (code "48") (name "Net-(U3-SW)") (class "Default")
      (node (ref "C38") (pin "2") (pinfunction "2_2") (pintype "unspecified"))
      (node (ref "L6") (pin "1") (pinfunction "1_1") (pintype "unspecified"))
      (node (ref "U3") (pin "6") (pinfunction "SW_6") (pintype "unspecified"))
    )
    (net (code "49") (name "Net-(U3-VCC)") (class "Default")
      (node (ref "C39") (pin "2") (pinfunction "2_2") (pintype "unspecified"))
      (node (ref "R32") (pin "1") (pinfunction "1_1") (pintype "unspecified"))
      (node (ref "U3") (pin "2") (pinfunction "VCC_2") (pintype "unspecified"))
    )
    (net (code "50") (name "Net-(U5-VCC2)") (class "Default")
      (node (ref "R2") (pin "1") (pinfunction "1_1") (pintype "unspecified"))
      (node (ref "U5") (pin "19") (pinfunction "VCC2_19") (pintype "unspecified"))
    )
    (net (code "51") (name "OUT") (class "Default")
      (node (ref "C28") (pin "2") (pinfunction "2_2") (pintype "unspecified"))
      (node (ref "C44") (pin "1") (pinfunction "1_1") (pintype "unspecified"))
    )
    (net (code "52") (name "PAEN") (class "Default")
      (node (ref "C36") (pin "2") (pinfunction "2_2") (pintype "unspecified"))
      (node (ref "C37") (pin "2") (pinfunction "2_2") (pintype "unspecified"))
      (node (ref "C46") (pin "2") (pinfunction "2_2") (pintype "unspecified"))
      (node (ref "C47") (pin "1") (pinfunction "1_1") (pintype "unspecified"))
      (node (ref "C48") (pin "1") (pinfunction "1_1") (pintype "unspecified"))
      (node (ref "C49") (pin "1") (pinfunction "1_1") (pintype "unspecified"))
      (node (ref "L6") (pin "2") (pinfunction "2_2") (pintype "unspecified"))
      (node (ref "R2") (pin "2") (pinfunction "2_2") (pintype "unspecified"))
      (node (ref "R27") (pin "2") (pinfunction "2_2") (pintype "unspecified"))
      (node (ref "U5") (pin "18") (pinfunction "VCC3_18") (pintype "unspecified"))
      (node (ref "U5") (pin "20") (pinfunction "VCC1_20") (pintype "unspecified"))
      (node (ref "U5") (pin "5") (pinfunction "PA_EN_5") (pintype "unspecified"))
    )
    (net (code "53") (name "PDET") (class "Default")
      (node (ref "C45") (pin "2") (pinfunction "2_2") (pintype "unspecified"))
      (node (ref "PDET") (pin "1") (pinfunction "1_1") (pintype "unspecified"))
      (node (ref "U5") (pin "10") (pinfunction "PDET_10") (pintype "unspecified"))
    )
    (net (code "54") (name "RFIN") (class "Default")
      (node (ref "C44") (pin "2") (pinfunction "2_2") (pintype "unspecified"))
      (node (ref "U5") (pin "3") (pinfunction "RF_IN_3") (pintype "unspecified"))
    )
    (net (code "55") (name "RFOUT") (class "Default")
      (node (ref "C43") (pin "2") (pinfunction "2_2") (pintype "unspecified"))
      (node (ref "U5") (pin "13") (pinfunction "RF_OUT_13") (pintype "unspecified"))
    )
    (net (code "56") (name "VCC") (class "Default")
      (node (ref "BX") (pin "2") (pinfunction "2_2") (pintype "unspecified"))
      (node (ref "C15") (pin "2") (pinfunction "2_2") (pintype "unspecified"))
      (node (ref "C25") (pin "2") (pinfunction "2_2") (pintype "unspecified"))
      (node (ref "C26") (pin "2") (pinfunction "2_2") (pintype "unspecified"))
      (node (ref "C34") (pin "2") (pinfunction "2_2") (pintype "unspecified"))
      (node (ref "C35") (pin "2") (pinfunction "2_2") (pintype "unspecified"))
      (node (ref "C6") (pin "2") (pinfunction "2_2") (pintype "unspecified"))
      (node (ref "C7") (pin "1") (pinfunction "1_1") (pintype "unspecified"))
      (node (ref "C8") (pin "1") (pinfunction "1_1") (pintype "unspecified"))
      (node (ref "CS0") (pin "2") (pinfunction "2_2") (pintype "unspecified"))
      (node (ref "CS1") (pin "2") (pinfunction "2_2") (pintype "unspecified"))
      (node (ref "CS2") (pin "2") (pinfunction "2_2") (pintype "unspecified"))
      (node (ref "L5") (pin "2") (pinfunction "2_2") (pintype "unspecified"))
      (node (ref "R20") (pin "2") (pinfunction "2_2") (pintype "unspecified"))
      (node (ref "R26") (pin "2") (pinfunction "2_2") (pintype "unspecified"))
      (node (ref "R29") (pin "2") (pinfunction "2_2") (pintype "unspecified"))
      (node (ref "R7") (pin "2") (pinfunction "2_2") (pintype "unspecified"))
      (node (ref "U1") (pin "22") (pinfunction "VDD3V3_22") (pintype "unspecified"))
      (node (ref "U1") (pin "30") (pinfunction "VDDVT_30") (pintype "unspecified"))
      (node (ref "U1") (pin "31") (pinfunction "BUFVDD_31") (pintype "unspecified"))
      (node (ref "U1") (pin "32") (pinfunction "PAVDD_32") (pintype "unspecified"))
      (node (ref "U1") (pin "39") (pinfunction "VCOVDD_39") (pintype "unspecified"))
      (node (ref "U1") (pin "8") (pinfunction "VDD33_DIG_8") (pintype "unspecified"))
      (node (ref "U1") (pin "9") (pinfunction "V2D5_PLL_9") (pintype "unspecified"))
    )
    (net (code "57") (name "VCC-IN") (class "Default")
      (node (ref "C30") (pin "2") (pinfunction "2_2") (pintype "unspecified"))
      (node (ref "C31") (pin "2") (pinfunction "2_2") (pintype "unspecified"))
      (node (ref "C4") (pin "2") (pinfunction "2_2") (pintype "unspecified"))
      (node (ref "C40") (pin "2") (pinfunction "2_2") (pintype "unspecified"))
      (node (ref "C41") (pin "2") (pinfunction "2_2") (pintype "unspecified"))
      (node (ref "C42") (pin "2") (pinfunction "2_2") (pintype "unspecified"))
      (node (ref "IN") (pin "1") (pinfunction "1_1") (pintype "unspecified"))
      (node (ref "R3") (pin "2") (pinfunction "2_2") (pintype "unspecified"))
      (node (ref "R33") (pin "2") (pinfunction "2_2") (pintype "unspecified"))
      (node (ref "U2") (pin "7") (pinfunction "IN_7") (pintype "unspecified"))
      (node (ref "U3") (pin "7") (pinfunction "IN_7") (pintype "unspecified"))
    )
    (net (code "58") (name "XTAL1") (class "Default")
      (node (ref "C12") (pin "1") (pinfunction "1_1") (pintype "unspecified"))
      (node (ref "U1") (pin "24") (pinfunction "XTAL1_24") (pintype "unspecified"))
      (node (ref "X1") (pin "2") (pinfunction "2_2") (pintype "unspecified"))
    )
    (net (code "59") (name "XTAL2") (class "Default")
      (node (ref "C13") (pin "1") (pinfunction "1_1") (pintype "unspecified"))
      (node (ref "U1") (pin "25") (pinfunction "XTAL2_25") (pintype "unspecified"))
      (node (ref "X1") (pin "1") (pinfunction "1_1") (pintype "unspecified"))
    )
    (net (code "60") (name "audio") (class "Default")
      (node (ref "AUDIO") (pin "1") (pinfunction "1_1") (pintype "unspecified"))
      (node (ref "R16") (pin "2") (pinfunction "2_2") (pintype "unspecified"))
    )
    (net (code "61") (name "unconnected-(U1-ACP1-Pad15)") (class "Default")
      (node (ref "U1") (pin "15") (pinfunction "ACP1_15") (pintype "unspecified+no_connect"))
    )
    (net (code "62") (name "unconnected-(U1-AOUT1-Pad16)") (class "Default")
      (node (ref "U1") (pin "16") (pinfunction "AOUT1_16") (pintype "unspecified+no_connect"))
    )
    (net (code "63") (name "unconnected-(U1-AVDD_6-Pad13)") (class "Default")
      (node (ref "U1") (pin "13") (pinfunction "AVDD_6_13") (pintype "unspecified+no_connect"))
    )
    (net (code "64") (name "unconnected-(U1-AVT1-Pad14)") (class "Default")
      (node (ref "U1") (pin "14") (pinfunction "AVT1_14") (pintype "unspecified+no_connect"))
    )
    (net (code "65") (name "unconnected-(U1-NC-Pad2)") (class "Default")
      (node (ref "U1") (pin "2") (pinfunction "NC_2") (pintype "unspecified+no_connect"))
    )
    (net (code "66") (name "unconnected-(U1-NC-Pad12)") (class "Default")
      (node (ref "U1") (pin "12") (pinfunction "NC_12") (pintype "unspecified+no_connect"))
    )
    (net (code "67") (name "unconnected-(U1-NC-Pad18)") (class "Default")
      (node (ref "U1") (pin "18") (pinfunction "NC_18") (pintype "unspecified+no_connect"))
    )
    (net (code "68") (name "unconnected-(U1-NC-Pad36)") (class "Default")
      (node (ref "U1") (pin "36") (pinfunction "NC_36") (pintype "unspecified+no_connect"))
    )
    (net (code "69") (name "unconnected-(U1-NC-Pad37)") (class "Default")
      (node (ref "U1") (pin "37") (pinfunction "NC_37") (pintype "unspecified+no_connect"))
    )
    (net (code "70") (name "unconnected-(U5-NC-Pad1)") (class "Default")
      (node (ref "U5") (pin "1") (pinfunction "NC_1") (pintype "unspecified+no_connect"))
    )
    (net (code "71") (name "unconnected-(U5-NC-Pad6)") (class "Default")
      (node (ref "U5") (pin "6") (pinfunction "NC_6") (pintype "unspecified+no_connect"))
    )
    (net (code "72") (name "unconnected-(U5-NC-Pad7)") (class "Default")
      (node (ref "U5") (pin "7") (pinfunction "NC_7") (pintype "unspecified+no_connect"))
    )
    (net (code "73") (name "unconnected-(U5-NC-Pad8)") (class "Default")
      (node (ref "U5") (pin "8") (pinfunction "NC_8") (pintype "unspecified+no_connect"))
    )
    (net (code "74") (name "unconnected-(U5-NC-Pad9)") (class "Default")
      (node (ref "U5") (pin "9") (pinfunction "NC_9") (pintype "unspecified+no_connect"))
    )
    (net (code "75") (name "video") (class "Default")
      (node (ref "C24") (pin "1") (pinfunction "1_1") (pintype "unspecified"))
      (node (ref "R23") (pin "1") (pinfunction "1_1") (pintype "unspecified"))
      (node (ref "R24") (pin "2") (pinfunction "2_2") (pintype "unspecified"))
      (node (ref "VIDEO") (pin "1") (pinfunction "1_1") (pintype "unspecified"))
    )
  )
)
